# esp8266-dev-ftdi.net
KiCad netlist of a schematic drawn in EAGLE
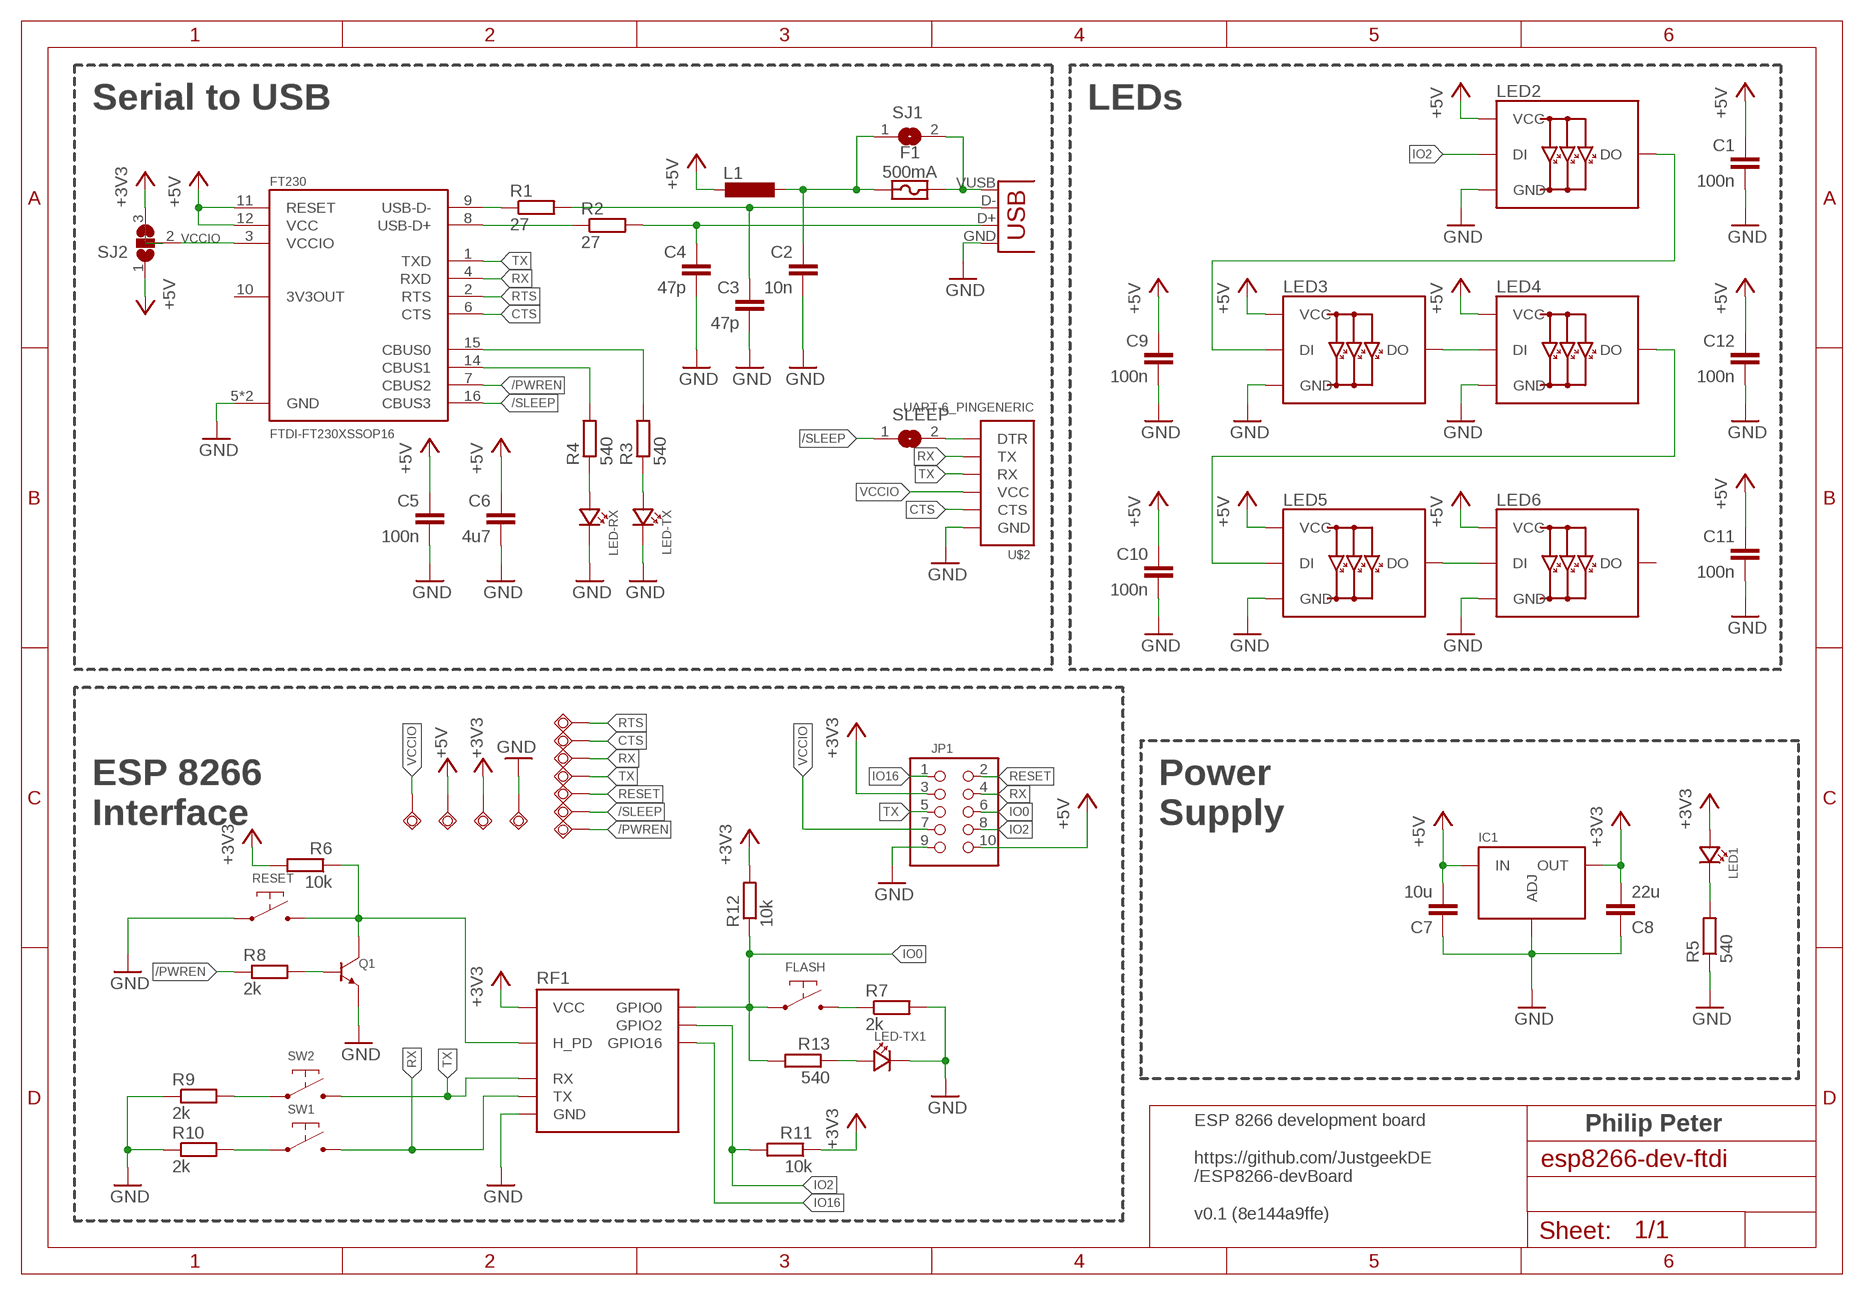
[diagram p0: schematic, sheet 1]

(export (version "E")
  (design (tool "Eeschema 10.0.6"))
  (components
    (comp (ref "3V3")
      (value "TPSQTP15R")
      (footprint "eagle-import:TP15R")
      (libsource (lib "eagle-import") (part "TPSQTP15R"))
    )
    (comp (ref "5V")
      (value "TPSQTP15R")
      (footprint "eagle-import:TP15R")
      (libsource (lib "eagle-import") (part "TPSQTP15R"))
    )
    (comp (ref "C1")
      (value "100n")
      (footprint "eagle-import:C0805")
      (libsource (lib "eagle-import") (part "C-EUC0805"))
    )
    (comp (ref "C2")
      (value "10n")
      (footprint "eagle-import:C0805")
      (libsource (lib "eagle-import") (part "C-EUC0805"))
    )
    (comp (ref "C3")
      (value "47p")
      (footprint "eagle-import:C0805")
      (libsource (lib "eagle-import") (part "C-EUC0805"))
    )
    (comp (ref "C4")
      (value "47p")
      (footprint "eagle-import:C0805")
      (libsource (lib "eagle-import") (part "C-EUC0805"))
    )
    (comp (ref "C5")
      (value "100n")
      (footprint "eagle-import:C0805")
      (libsource (lib "eagle-import") (part "C-EUC0805"))
    )
    (comp (ref "C6")
      (value "4u7")
      (footprint "eagle-import:C0805")
      (libsource (lib "eagle-import") (part "C-EUC0805"))
    )
    (comp (ref "C7")
      (value "10u")
      (footprint "eagle-import:C0805")
      (libsource (lib "eagle-import") (part "C-EUC0805"))
    )
    (comp (ref "C8")
      (value "22u")
      (footprint "eagle-import:C0805")
      (libsource (lib "eagle-import") (part "C-EUC0805"))
    )
    (comp (ref "C9")
      (value "100n")
      (footprint "eagle-import:C0805")
      (libsource (lib "eagle-import") (part "C-EUC0805"))
    )
    (comp (ref "C10")
      (value "100n")
      (footprint "eagle-import:C0805")
      (libsource (lib "eagle-import") (part "C-EUC0805"))
    )
    (comp (ref "C11")
      (value "100n")
      (footprint "eagle-import:C0805")
      (libsource (lib "eagle-import") (part "C-EUC0805"))
    )
    (comp (ref "C12")
      (value "100n")
      (footprint "eagle-import:C0805")
      (libsource (lib "eagle-import") (part "C-EUC0805"))
    )
    (comp (ref "CON1")
      (value "USBMICRO-NO_CENTER-LONG_PADS")
      (footprint "eagle-import:USB-MICRO-SMD-NO_CENTER-LONG_PADS")
      (libsource (lib "eagle-import") (part "USBMICRO-NO_CENTER-LONG_PADS"))
    )
    (comp (ref "CTS")
      (value "TPSQTP15R")
      (footprint "eagle-import:TP15R")
      (libsource (lib "eagle-import") (part "TPSQTP15R"))
    )
    (comp (ref "F1")
      (value "500mA")
      (footprint "eagle-import:SMD-FUSE-0805")
      (libsource (lib "eagle-import") (part "FUSE0805"))
    )
    (comp (ref "FLASH")
      (value "SWITCH-DEFAULT_OFF-DEFAULT")
      (footprint "eagle-import:SWITCH-GENERIC-4_PIN")
      (libsource (lib "eagle-import") (part "SWITCH-DEFAULT_OFF-DEFAULT"))
    )
    (comp (ref "FT230")
      (value "FTDI-FT230XSSOP16")
      (footprint "eagle-import:SSOP-16-FTDI")
      (libsource (lib "eagle-import") (part "FTDI-FT230XSSOP16"))
    )
    (comp (ref "GND")
      (value "TPSQTP15R")
      (footprint "eagle-import:TP15R")
      (libsource (lib "eagle-import") (part "TPSQTP15R"))
    )
    (comp (ref "IC1")
      (value "REGULATOR-LM317-SOT223")
      (footprint "eagle-import:SOT223")
      (libsource (lib "eagle-import") (part "REGULATOR-LM317-SOT223"))
    )
    (comp (ref "JP1")
      (value "GENERIC-2X5")
      (footprint "eagle-import:PINHEADER-100MIL-2X5-NOSILK")
      (libsource (lib "eagle-import") (part "GENERIC-2X5"))
    )
    (comp (ref "L1")
      (value "875-MI0805K601R-10")
      (footprint "eagle-import:R0805")
      (libsource (lib "eagle-import") (part "INDUCTOR0805"))
    )
    (comp (ref "LED-RX")
      (value "LED0805")
      (footprint "eagle-import:CHIPLED_0805")
      (libsource (lib "eagle-import") (part "LED0805"))
    )
    (comp (ref "LED-TX")
      (value "LED0805")
      (footprint "eagle-import:CHIPLED_0805")
      (libsource (lib "eagle-import") (part "LED0805"))
    )
    (comp (ref "LED-TX1")
      (value "LED0805")
      (footprint "eagle-import:CHIPLED_0805")
      (libsource (lib "eagle-import") (part "LED0805"))
    )
    (comp (ref "LED1")
      (value "LED0805")
      (footprint "eagle-import:CHIPLED_0805")
      (libsource (lib "eagle-import") (part "LED0805"))
    )
    (comp (ref "LED2")
      (value "WS2812B")
      (footprint "eagle-import:CHIP-5050-4_PIN")
      (libsource (lib "eagle-import") (part "WS2812B"))
    )
    (comp (ref "LED3")
      (value "WS2812B")
      (footprint "eagle-import:CHIP-5050-4_PIN")
      (libsource (lib "eagle-import") (part "WS2812B"))
    )
    (comp (ref "LED4")
      (value "WS2812B")
      (footprint "eagle-import:CHIP-5050-4_PIN")
      (libsource (lib "eagle-import") (part "WS2812B"))
    )
    (comp (ref "LED5")
      (value "WS2812B")
      (footprint "eagle-import:CHIP-5050-4_PIN")
      (libsource (lib "eagle-import") (part "WS2812B"))
    )
    (comp (ref "LED6")
      (value "WS2812B")
      (footprint "eagle-import:CHIP-5050-4_PIN")
      (libsource (lib "eagle-import") (part "WS2812B"))
    )
    (comp (ref "PEN")
      (value "TPSQTP15R")
      (footprint "eagle-import:TP15R")
      (libsource (lib "eagle-import") (part "TPSQTP15R"))
    )
    (comp (ref "Q1")
      (value "TRANSISTOR-NPN-GENERIC-SOT23-BEC")
      (footprint "eagle-import:SOT23")
      (libsource (lib "eagle-import") (part "TRANSISTOR-NPN-GENERIC-SOT23-BEC"))
    )
    (comp (ref "R1")
      (value "27")
      (footprint "eagle-import:R0805")
      (libsource (lib "eagle-import") (part "R-EU_R0805"))
    )
    (comp (ref "R2")
      (value "27")
      (footprint "eagle-import:R0805")
      (libsource (lib "eagle-import") (part "R-EU_R0805"))
    )
    (comp (ref "R3")
      (value "540")
      (footprint "eagle-import:R0805")
      (libsource (lib "eagle-import") (part "R-EU_R0805"))
    )
    (comp (ref "R4")
      (value "540")
      (footprint "eagle-import:R0805")
      (libsource (lib "eagle-import") (part "R-EU_R0805"))
    )
    (comp (ref "R5")
      (value "540")
      (footprint "eagle-import:R0805")
      (libsource (lib "eagle-import") (part "R-EU_R0805"))
    )
    (comp (ref "R6")
      (value "10k")
      (footprint "eagle-import:R0805")
      (libsource (lib "eagle-import") (part "R-EU_R0805"))
    )
    (comp (ref "R7")
      (value "2k")
      (footprint "eagle-import:R0805")
      (libsource (lib "eagle-import") (part "R-EU_R0805"))
    )
    (comp (ref "R8")
      (value "2k")
      (footprint "eagle-import:R0805")
      (libsource (lib "eagle-import") (part "R-EU_R0805"))
    )
    (comp (ref "R9")
      (value "2k")
      (footprint "eagle-import:R0805")
      (libsource (lib "eagle-import") (part "R-EU_R0805"))
    )
    (comp (ref "R10")
      (value "2k")
      (footprint "eagle-import:R0805")
      (libsource (lib "eagle-import") (part "R-EU_R0805"))
    )
    (comp (ref "R11")
      (value "10k")
      (footprint "eagle-import:R0805")
      (libsource (lib "eagle-import") (part "R-EU_R0805"))
    )
    (comp (ref "R12")
      (value "10k")
      (footprint "eagle-import:R0805")
      (libsource (lib "eagle-import") (part "R-EU_R0805"))
    )
    (comp (ref "R13")
      (value "540")
      (footprint "eagle-import:R0805")
      (libsource (lib "eagle-import") (part "R-EU_R0805"))
    )
    (comp (ref "RES")
      (value "TPSQTP15R")
      (footprint "eagle-import:TP15R")
      (libsource (lib "eagle-import") (part "TPSQTP15R"))
    )
    (comp (ref "RESET")
      (value "SWITCH-DEFAULT_OFF-2PIN")
      (footprint "eagle-import:SWITCH-GENERIC-2_PIN")
      (libsource (lib "eagle-import") (part "SWITCH-DEFAULT_OFF-2PIN"))
    )
    (comp (ref "RF1")
      (value "ESP2866-ESP-01THT")
      (footprint "eagle-import:ESP8266-ESP-01")
      (libsource (lib "eagle-import") (part "ESP2866-ESP-01THT"))
    )
    (comp (ref "RTS")
      (value "TPSQTP15R")
      (footprint "eagle-import:TP15R")
      (libsource (lib "eagle-import") (part "TPSQTP15R"))
    )
    (comp (ref "RX")
      (value "TPSQTP15R")
      (footprint "eagle-import:TP15R")
      (libsource (lib "eagle-import") (part "TPSQTP15R"))
    )
    (comp (ref "SJ1") (value "SJ") (footprint "eagle-import:SJ") (libsource (lib "eagle-import") (part "SJ")))
    (comp (ref "SJ2")
      (value "SJ2W")
      (footprint "eagle-import:SJ_2")
      (libsource (lib "eagle-import") (part "SJ2W"))
    )
    (comp (ref "SLE")
      (value "TPSQTP15R")
      (footprint "eagle-import:TP15R")
      (libsource (lib "eagle-import") (part "TPSQTP15R"))
    )
    (comp (ref "SLEEP")
      (value "SJ")
      (footprint "eagle-import:SJ")
      (libsource (lib "eagle-import") (part "SJ"))
    )
    (comp (ref "SW1")
      (value "SWITCH-DEFAULT_OFF-2PIN")
      (footprint "eagle-import:SWITCH-GENERIC-2_PIN")
      (libsource (lib "eagle-import") (part "SWITCH-DEFAULT_OFF-2PIN"))
    )
    (comp (ref "SW2")
      (value "SWITCH-DEFAULT_OFF-2PIN")
      (footprint "eagle-import:SWITCH-GENERIC-2_PIN")
      (libsource (lib "eagle-import") (part "SWITCH-DEFAULT_OFF-2PIN"))
    )
    (comp (ref "TX")
      (value "TPSQTP15R")
      (footprint "eagle-import:TP15R")
      (libsource (lib "eagle-import") (part "TPSQTP15R"))
    )
    (comp (ref "U$2")
      (value "UART-6_PINGENERIC")
      (footprint "eagle-import:PINHEADER-100MIL-1X6")
      (libsource (lib "eagle-import") (part "UART-6_PINGENERIC"))
    )
    (comp (ref "VCC")
      (value "TPSQTP15R")
      (footprint "eagle-import:TP15R")
      (libsource (lib "eagle-import") (part "TPSQTP15R"))
    )
  )
  (nets
    (net (code "1") (name "+3V3") (class "Default")
      (node (ref "3V3") (pin "TP") (pinfunction "TP_TP") (pintype "input"))
      (node (ref "C8") (pin "2") (pinfunction "2_2") (pintype "passive"))
      (node (ref "IC1") (pin "2") (pinfunction "OUT_2") (pintype "bidirectional"))
      (node (ref "IC1") (pin "4") (pinfunction "OUT_4") (pintype "bidirectional"))
      (node (ref "JP1") (pin "3") (pinfunction "3_3") (pintype "bidirectional"))
      (node (ref "LED1") (pin "A") (pinfunction "A_A") (pintype "bidirectional"))
      (node (ref "R11") (pin "1") (pinfunction "1_1") (pintype "passive"))
      (node (ref "R12") (pin "2") (pinfunction "2_2") (pintype "passive"))
      (node (ref "R6") (pin "2") (pinfunction "2_2") (pintype "passive"))
      (node (ref "RF1") (pin "VCC") (pinfunction "VCC_VCC") (pintype "bidirectional"))
      (node (ref "SJ2") (pin "3") (pinfunction "3_3") (pintype "passive"))
    )
    (net (code "2") (name "+5V") (class "Default")
      (node (ref "5V") (pin "TP") (pinfunction "TP_TP") (pintype "input"))
      (node (ref "C1") (pin "1") (pinfunction "1_1") (pintype "passive"))
      (node (ref "C10") (pin "1") (pinfunction "1_1") (pintype "passive"))
      (node (ref "C11") (pin "1") (pinfunction "1_1") (pintype "passive"))
      (node (ref "C12") (pin "1") (pinfunction "1_1") (pintype "passive"))
      (node (ref "C5") (pin "1") (pinfunction "1_1") (pintype "passive"))
      (node (ref "C6") (pin "1") (pinfunction "1_1") (pintype "passive"))
      (node (ref "C7") (pin "2") (pinfunction "2_2") (pintype "passive"))
      (node (ref "C9") (pin "1") (pinfunction "1_1") (pintype "passive"))
      (node (ref "FT230") (pin "11") (pinfunction "RESET_11") (pintype "bidirectional"))
      (node (ref "FT230") (pin "12") (pinfunction "VCC_12") (pintype "bidirectional"))
      (node (ref "IC1") (pin "3") (pinfunction "IN_3") (pintype "bidirectional"))
      (node (ref "JP1") (pin "10") (pinfunction "10_10") (pintype "bidirectional"))
      (node (ref "L1") (pin "2") (pinfunction "2_2") (pintype "passive"))
      (node (ref "LED2") (pin "P$1") (pinfunction "VCC_P$1") (pintype "bidirectional"))
      (node (ref "LED3") (pin "P$1") (pinfunction "VCC_P$1") (pintype "bidirectional"))
      (node (ref "LED4") (pin "P$1") (pinfunction "VCC_P$1") (pintype "bidirectional"))
      (node (ref "LED5") (pin "P$1") (pinfunction "VCC_P$1") (pintype "bidirectional"))
      (node (ref "LED6") (pin "P$1") (pinfunction "VCC_P$1") (pintype "bidirectional"))
      (node (ref "SJ2") (pin "1") (pinfunction "1_1") (pintype "passive"))
    )
    (net (code "3") (name "CTS") (class "Default")
      (node (ref "CTS") (pin "TP") (pinfunction "TP_TP") (pintype "input"))
      (node (ref "FT230") (pin "6") (pinfunction "CTS_6") (pintype "bidirectional"))
      (node (ref "U$2") (pin "2") (pinfunction "CTS_2") (pintype "bidirectional"))
    )
    (net (code "4") (name "GND") (class "Default")
      (node (ref "C1") (pin "2") (pinfunction "2_2") (pintype "passive"))
      (node (ref "C10") (pin "2") (pinfunction "2_2") (pintype "passive"))
      (node (ref "C11") (pin "2") (pinfunction "2_2") (pintype "passive"))
      (node (ref "C12") (pin "2") (pinfunction "2_2") (pintype "passive"))
      (node (ref "C2") (pin "2") (pinfunction "2_2") (pintype "passive"))
      (node (ref "C3") (pin "2") (pinfunction "2_2") (pintype "passive"))
      (node (ref "C4") (pin "2") (pinfunction "2_2") (pintype "passive"))
      (node (ref "C5") (pin "2") (pinfunction "2_2") (pintype "passive"))
      (node (ref "C6") (pin "2") (pinfunction "2_2") (pintype "passive"))
      (node (ref "C7") (pin "1") (pinfunction "1_1") (pintype "passive"))
      (node (ref "C8") (pin "1") (pinfunction "1_1") (pintype "passive"))
      (node (ref "C9") (pin "2") (pinfunction "2_2") (pintype "passive"))
      (node (ref "CON1") (pin "GND") (pinfunction "GND_GND") (pintype "bidirectional"))
      (node (ref "FT230") (pin "13") (pinfunction "GND_13") (pintype "bidirectional"))
      (node (ref "FT230") (pin "5") (pinfunction "GND_5") (pintype "bidirectional"))
      (node (ref "GND") (pin "TP") (pinfunction "TP_TP") (pintype "input"))
      (node (ref "IC1") (pin "1") (pinfunction "ADJ_1") (pintype "bidirectional"))
      (node (ref "JP1") (pin "9") (pinfunction "9_9") (pintype "bidirectional"))
      (node (ref "LED-RX") (pin "C") (pinfunction "C_C") (pintype "bidirectional"))
      (node (ref "LED-TX") (pin "C") (pinfunction "C_C") (pintype "bidirectional"))
      (node (ref "LED-TX1") (pin "C") (pinfunction "C_C") (pintype "bidirectional"))
      (node (ref "LED2") (pin "P$3") (pinfunction "GND_P$3") (pintype "bidirectional"))
      (node (ref "LED3") (pin "P$3") (pinfunction "GND_P$3") (pintype "bidirectional"))
      (node (ref "LED4") (pin "P$3") (pinfunction "GND_P$3") (pintype "bidirectional"))
      (node (ref "LED5") (pin "P$3") (pinfunction "GND_P$3") (pintype "bidirectional"))
      (node (ref "LED6") (pin "P$3") (pinfunction "GND_P$3") (pintype "bidirectional"))
      (node (ref "Q1") (pin "P$2") (pinfunction "EMITTER_P$2") (pintype "bidirectional"))
      (node (ref "R10") (pin "1") (pinfunction "1_1") (pintype "passive"))
      (node (ref "R5") (pin "1") (pinfunction "1_1") (pintype "passive"))
      (node (ref "R7") (pin "2") (pinfunction "2_2") (pintype "passive"))
      (node (ref "R9") (pin "1") (pinfunction "1_1") (pintype "passive"))
      (node (ref "RESET") (pin "P$1") (pinfunction "P$1_P$1") (pintype "bidirectional"))
      (node (ref "RF1") (pin "GND") (pinfunction "GND_GND") (pintype "bidirectional"))
      (node (ref "U$2") (pin "1") (pinfunction "GND_1") (pintype "bidirectional"))
    )
    (net (code "5") (name "IO0") (class "Default")
      (node (ref "FLASH") (pin "P$1") (pinfunction "P$1_P$1") (pintype "bidirectional"))
      (node (ref "FLASH") (pin "P$2") (pinfunction "P$1_P$2") (pintype "bidirectional"))
      (node (ref "JP1") (pin "6") (pinfunction "6_6") (pintype "bidirectional"))
      (node (ref "R12") (pin "1") (pinfunction "1_1") (pintype "passive"))
      (node (ref "R13") (pin "2") (pinfunction "2_2") (pintype "passive"))
      (node (ref "RF1") (pin "GPIO0") (pinfunction "GPIO0_GPIO0") (pintype "bidirectional"))
    )
    (net (code "6") (name "IO2") (class "Default")
      (node (ref "JP1") (pin "8") (pinfunction "8_8") (pintype "bidirectional"))
      (node (ref "LED2") (pin "P$4") (pinfunction "DI_P$4") (pintype "bidirectional"))
      (node (ref "R11") (pin "2") (pinfunction "2_2") (pintype "passive"))
      (node (ref "RF1") (pin "GPIO2") (pinfunction "GPIO2_GPIO2") (pintype "bidirectional"))
    )
    (net (code "7") (name "IO16") (class "Default")
      (node (ref "JP1") (pin "1") (pinfunction "1_1") (pintype "bidirectional"))
      (node (ref "RF1") (pin "GPIO16") (pinfunction "GPIO16_GPIO16") (pintype "bidirectional"))
    )
    (net (code "8") (name "Net-(C3-Pad1)") (class "Default")
      (node (ref "C3") (pin "1") (pinfunction "1_1") (pintype "passive"))
      (node (ref "CON1") (pin "D-") (pinfunction "D-_D-") (pintype "bidirectional"))
      (node (ref "R1") (pin "2") (pinfunction "2_2") (pintype "passive"))
    )
    (net (code "9") (name "Net-(C4-Pad1)") (class "Default")
      (node (ref "C4") (pin "1") (pinfunction "1_1") (pintype "passive"))
      (node (ref "CON1") (pin "D+") (pinfunction "D+_D+") (pintype "bidirectional"))
      (node (ref "R2") (pin "2") (pinfunction "2_2") (pintype "passive"))
    )
    (net (code "10") (name "Net-(CON1-VBUS)") (class "Default")
      (node (ref "CON1") (pin "VUSB") (pinfunction "VBUS_VUSB") (pintype "bidirectional"))
      (node (ref "F1") (pin "2") (pinfunction "P$2_2") (pintype "bidirectional"))
      (node (ref "SJ1") (pin "2") (pinfunction "2_2") (pintype "passive"))
    )
    (net (code "11") (name "Net-(F1-P$1)") (class "Default")
      (node (ref "C2") (pin "1") (pinfunction "1_1") (pintype "passive"))
      (node (ref "F1") (pin "1") (pinfunction "P$1_1") (pintype "bidirectional"))
      (node (ref "L1") (pin "1") (pinfunction "1_1") (pintype "passive"))
      (node (ref "SJ1") (pin "1") (pinfunction "1_1") (pintype "passive"))
    )
    (net (code "12") (name "Net-(FLASH-P$2-PadP$3)") (class "Default")
      (node (ref "FLASH") (pin "P$3") (pinfunction "P$2_P$3") (pintype "bidirectional"))
      (node (ref "FLASH") (pin "P$4") (pinfunction "P$2_P$4") (pintype "bidirectional"))
      (node (ref "R7") (pin "1") (pinfunction "1_1") (pintype "passive"))
    )
    (net (code "13") (name "Net-(FT230-CBUS0)") (class "Default")
      (node (ref "FT230") (pin "15") (pinfunction "CBUS0_15") (pintype "bidirectional"))
      (node (ref "R3") (pin "2") (pinfunction "2_2") (pintype "passive"))
    )
    (net (code "14") (name "Net-(FT230-CBUS1)") (class "Default")
      (node (ref "FT230") (pin "14") (pinfunction "CBUS1_14") (pintype "bidirectional"))
      (node (ref "R4") (pin "2") (pinfunction "2_2") (pintype "passive"))
    )
    (net (code "15") (name "Net-(FT230-USB-D+)") (class "Default")
      (node (ref "FT230") (pin "8") (pinfunction "USB-D+_8") (pintype "bidirectional"))
      (node (ref "R2") (pin "1") (pinfunction "1_1") (pintype "passive"))
    )
    (net (code "16") (name "Net-(FT230-USB-D-)") (class "Default")
      (node (ref "FT230") (pin "9") (pinfunction "USB-D-_9") (pintype "bidirectional"))
      (node (ref "R1") (pin "1") (pinfunction "1_1") (pintype "passive"))
    )
    (net (code "17") (name "Net-(LED-RX-PadA)") (class "Default")
      (node (ref "LED-RX") (pin "A") (pinfunction "A_A") (pintype "bidirectional"))
      (node (ref "R4") (pin "1") (pinfunction "1_1") (pintype "passive"))
    )
    (net (code "18") (name "Net-(LED-TX-PadA)") (class "Default")
      (node (ref "LED-TX") (pin "A") (pinfunction "A_A") (pintype "bidirectional"))
      (node (ref "R3") (pin "1") (pinfunction "1_1") (pintype "passive"))
    )
    (net (code "19") (name "Net-(LED-TX1-PadA)") (class "Default")
      (node (ref "LED-TX1") (pin "A") (pinfunction "A_A") (pintype "bidirectional"))
      (node (ref "R13") (pin "1") (pinfunction "1_1") (pintype "passive"))
    )
    (net (code "20") (name "Net-(LED1-PadC)") (class "Default")
      (node (ref "LED1") (pin "C") (pinfunction "C_C") (pintype "bidirectional"))
      (node (ref "R5") (pin "2") (pinfunction "2_2") (pintype "passive"))
    )
    (net (code "21") (name "Net-(LED2-DO)") (class "Default")
      (node (ref "LED2") (pin "P$2") (pinfunction "DO_P$2") (pintype "bidirectional"))
      (node (ref "LED3") (pin "P$4") (pinfunction "DI_P$4") (pintype "bidirectional"))
    )
    (net (code "22") (name "Net-(LED3-DO)") (class "Default")
      (node (ref "LED3") (pin "P$2") (pinfunction "DO_P$2") (pintype "bidirectional"))
      (node (ref "LED4") (pin "P$4") (pinfunction "DI_P$4") (pintype "bidirectional"))
    )
    (net (code "23") (name "Net-(LED4-DO)") (class "Default")
      (node (ref "LED4") (pin "P$2") (pinfunction "DO_P$2") (pintype "bidirectional"))
      (node (ref "LED5") (pin "P$4") (pinfunction "DI_P$4") (pintype "bidirectional"))
    )
    (net (code "24") (name "Net-(LED5-DO)") (class "Default")
      (node (ref "LED5") (pin "P$2") (pinfunction "DO_P$2") (pintype "bidirectional"))
      (node (ref "LED6") (pin "P$4") (pinfunction "DI_P$4") (pintype "bidirectional"))
    )
    (net (code "25") (name "Net-(Q1-BASE)") (class "Default")
      (node (ref "Q1") (pin "P$1") (pinfunction "BASE_P$1") (pintype "bidirectional"))
      (node (ref "R8") (pin "2") (pinfunction "2_2") (pintype "passive"))
    )
    (net (code "26") (name "Net-(R9-Pad2)") (class "Default")
      (node (ref "R9") (pin "2") (pinfunction "2_2") (pintype "passive"))
      (node (ref "SW2") (pin "P$1") (pinfunction "P$1_P$1") (pintype "bidirectional"))
    )
    (net (code "27") (name "Net-(R10-Pad2)") (class "Default")
      (node (ref "R10") (pin "2") (pinfunction "2_2") (pintype "passive"))
      (node (ref "SW1") (pin "P$1") (pinfunction "P$1_P$1") (pintype "bidirectional"))
    )
    (net (code "28") (name "Net-(U$2-DTR)") (class "Default")
      (node (ref "SLEEP") (pin "2") (pinfunction "2_2") (pintype "passive"))
      (node (ref "U$2") (pin "6") (pinfunction "DTR_6") (pintype "bidirectional"))
    )
    (net (code "29") (name "RESET") (class "Default")
      (node (ref "JP1") (pin "2") (pinfunction "2_2") (pintype "bidirectional"))
      (node (ref "Q1") (pin "P$3") (pinfunction "COLLECTOR_P$3") (pintype "bidirectional"))
      (node (ref "R6") (pin "1") (pinfunction "1_1") (pintype "passive"))
      (node (ref "RES") (pin "TP") (pinfunction "TP_TP") (pintype "input"))
      (node (ref "RESET") (pin "P$2") (pinfunction "P$2_P$2") (pintype "bidirectional"))
      (node (ref "RF1") (pin "H_PD") (pinfunction "H_PD_H_PD") (pintype "bidirectional"))
    )
    (net (code "30") (name "RTS") (class "Default")
      (node (ref "FT230") (pin "2") (pinfunction "RTS_2") (pintype "bidirectional"))
      (node (ref "RTS") (pin "TP") (pinfunction "TP_TP") (pintype "input"))
    )
    (net (code "31") (name "RX") (class "Default")
      (node (ref "FT230") (pin "4") (pinfunction "RXD_4") (pintype "bidirectional"))
      (node (ref "JP1") (pin "4") (pinfunction "4_4") (pintype "bidirectional"))
      (node (ref "RF1") (pin "TX") (pinfunction "TX_TX") (pintype "bidirectional"))
      (node (ref "RX") (pin "TP") (pinfunction "TP_TP") (pintype "input"))
      (node (ref "SW1") (pin "P$2") (pinfunction "P$2_P$2") (pintype "bidirectional"))
      (node (ref "U$2") (pin "5") (pinfunction "TX_5") (pintype "bidirectional"))
    )
    (net (code "32") (name "TX") (class "Default")
      (node (ref "FT230") (pin "1") (pinfunction "TXD_1") (pintype "bidirectional"))
      (node (ref "JP1") (pin "5") (pinfunction "5_5") (pintype "bidirectional"))
      (node (ref "RF1") (pin "RX") (pinfunction "RX_RX") (pintype "bidirectional"))
      (node (ref "SW2") (pin "P$2") (pinfunction "P$2_P$2") (pintype "bidirectional"))
      (node (ref "TX") (pin "TP") (pinfunction "TP_TP") (pintype "input"))
      (node (ref "U$2") (pin "4") (pinfunction "RX_4") (pintype "bidirectional"))
    )
    (net (code "33") (name "VCCIO") (class "Default")
      (node (ref "FT230") (pin "3") (pinfunction "VCCIO_3") (pintype "bidirectional"))
      (node (ref "JP1") (pin "7") (pinfunction "7_7") (pintype "bidirectional"))
      (node (ref "SJ2") (pin "2") (pinfunction "2_2") (pintype "passive"))
      (node (ref "U$2") (pin "3") (pinfunction "VCC_3") (pintype "bidirectional"))
      (node (ref "VCC") (pin "TP") (pinfunction "TP_TP") (pintype "input"))
    )
    (net (code "34") (name "unconnected-(FT230-3V3OUT-Pad10)") (class "Default")
      (node (ref "FT230") (pin "10") (pinfunction "3V3OUT_10") (pintype "bidirectional"))
    )
    (net (code "35") (name "unconnected-(LED6-DO-PadP$2)") (class "Default")
      (node (ref "LED6") (pin "P$2") (pinfunction "DO_P$2") (pintype "bidirectional"))
    )
    (net (code "36") (name "{slash}PWREN") (class "Default")
      (node (ref "FT230") (pin "7") (pinfunction "CBUS2_7") (pintype "bidirectional"))
      (node (ref "PEN") (pin "TP") (pinfunction "TP_TP") (pintype "input"))
      (node (ref "R8") (pin "1") (pinfunction "1_1") (pintype "passive"))
    )
    (net (code "37") (name "{slash}SLEEP") (class "Default")
      (node (ref "FT230") (pin "16") (pinfunction "CBUS3_16") (pintype "bidirectional"))
      (node (ref "SLE") (pin "TP") (pinfunction "TP_TP") (pintype "input"))
      (node (ref "SLEEP") (pin "1") (pinfunction "1_1") (pintype "passive"))
    )
  )
)
